# Eagle_TouchSensor.net
KiCad netlist of a schematic drawn in EAGLE
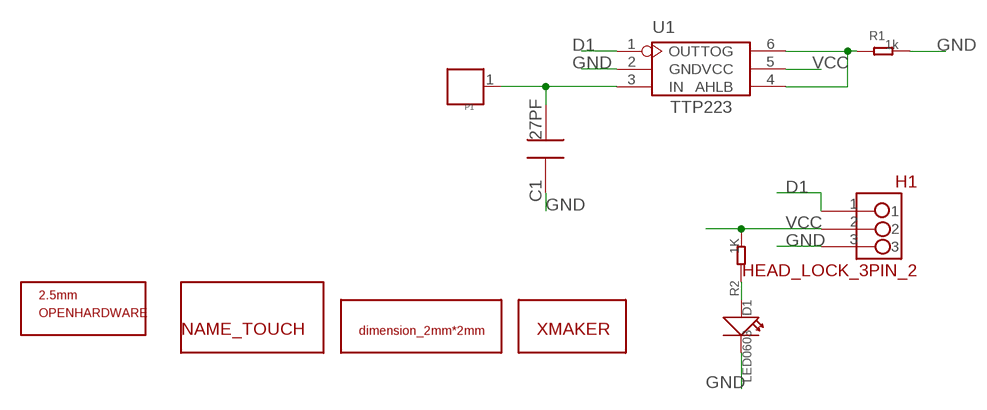
[diagram p0: schematic, sheet 1]

(export (version "E")
  (design (tool "Eeschema 10.0.6"))
  (components
    (comp (ref "C1")
      (value "27PF")
      (footprint "eagle-import:0603")
      (libsource (lib "eagle-import") (part "C0603"))
    )
    (comp (ref "D1")
      (value "LED0603")
      (footprint "eagle-import:LED0603")
      (libsource (lib "eagle-import") (part "LED0603"))
    )
    (comp (ref "H1")
      (value "HEAD_LOCK_3PIN_2")
      (footprint "eagle-import:HEAD_LOCK_3PIN_2")
      (libsource (lib "eagle-import") (part "HEAD_LOCK_3PIN_2"))
    )
    (comp (ref "P1")
      (value "PAD'D450MIL'")
      (footprint "eagle-import:1P-D450")
      (libsource (lib "eagle-import") (part "PAD'D450MIL'"))
    )
    (comp (ref "R1")
      (value "1k")
      (footprint "eagle-import:0603")
      (libsource (lib "eagle-import") (part "R0603"))
    )
    (comp (ref "R2")
      (value "1K")
      (footprint "eagle-import:0603")
      (libsource (lib "eagle-import") (part "R0603"))
    )
    (comp (ref "U$1")
      (value "XMAKERLOGO")
      (footprint "eagle-import:XMAKERLOGO")
      (libsource (lib "eagle-import") (part "XMAKERLOGO"))
    )
    (comp (ref "U$3")
      (value "DIMENSION_2MM2MM")
      (footprint "eagle-import:DIMENSION_2MM_2MM")
      (libsource (lib "eagle-import") (part "DIMENSION_2MM2MM"))
    )
    (comp (ref "U$4")
      (value "NAME_TOUCH")
      (footprint "eagle-import:NAME_TOUCH")
      (libsource (lib "eagle-import") (part "NAME_TOUCH"))
    )
    (comp (ref "U$5")
      (value "OPENHARDWARE_2.5MM_TOP")
      (footprint "eagle-import:OPENSOURCELOGO_2.5MM")
      (libsource (lib "eagle-import") (part "OPENHARDWARE_2.5MM_TOP"))
    )
    (comp (ref "U1")
      (value "TTP223")
      (footprint "eagle-import:SOT23-6L")
      (libsource (lib "eagle-import") (part "TTP223"))
    )
  )
  (nets
    (net (code "1") (name "/D1") (class "Default")
      (node (ref "H1") (pin "1") (pinfunction "1_1") (pintype "passive"))
      (node (ref "U1") (pin "1") (pinfunction "OUT_1") (pintype "bidirectional"))
    )
    (net (code "2") (name "/GND") (class "Default")
      (node (ref "C1") (pin "1") (pinfunction "1_1") (pintype "bidirectional"))
      (node (ref "D1") (pin "2") (pinfunction "-_2") (pintype "bidirectional"))
      (node (ref "H1") (pin "3") (pinfunction "3_3") (pintype "passive"))
      (node (ref "R1") (pin "2") (pinfunction "2_2") (pintype "bidirectional"))
      (node (ref "U1") (pin "2") (pinfunction "GND_2") (pintype "bidirectional"))
    )
    (net (code "3") (name "/VCC") (class "Default")
      (node (ref "H1") (pin "2") (pinfunction "2_2") (pintype "passive"))
      (node (ref "R2") (pin "2") (pinfunction "2_2") (pintype "bidirectional"))
      (node (ref "U1") (pin "5") (pinfunction "VCC_5") (pintype "bidirectional"))
    )
    (net (code "4") (name "Net-(D1-+)") (class "Default")
      (node (ref "D1") (pin "1") (pinfunction "+_1") (pintype "bidirectional"))
      (node (ref "R2") (pin "1") (pinfunction "1_1") (pintype "bidirectional"))
    )
    (net (code "5") (name "Net-(P1-P$1)") (class "Default")
      (node (ref "C1") (pin "2") (pinfunction "2_2") (pintype "bidirectional"))
      (node (ref "P1") (pin "1") (pinfunction "P$1_1") (pintype "bidirectional"))
      (node (ref "U1") (pin "3") (pinfunction "IN_3") (pintype "bidirectional"))
    )
    (net (code "6") (name "Net-(U1-AHLB)") (class "Default")
      (node (ref "R1") (pin "1") (pinfunction "1_1") (pintype "bidirectional"))
      (node (ref "U1") (pin "4") (pinfunction "AHLB_4") (pintype "bidirectional"))
      (node (ref "U1") (pin "6") (pinfunction "TOG_6") (pintype "bidirectional"))
    )
  )
)
